# rev1.net
KiCad netlist of a schematic drawn in EAGLE
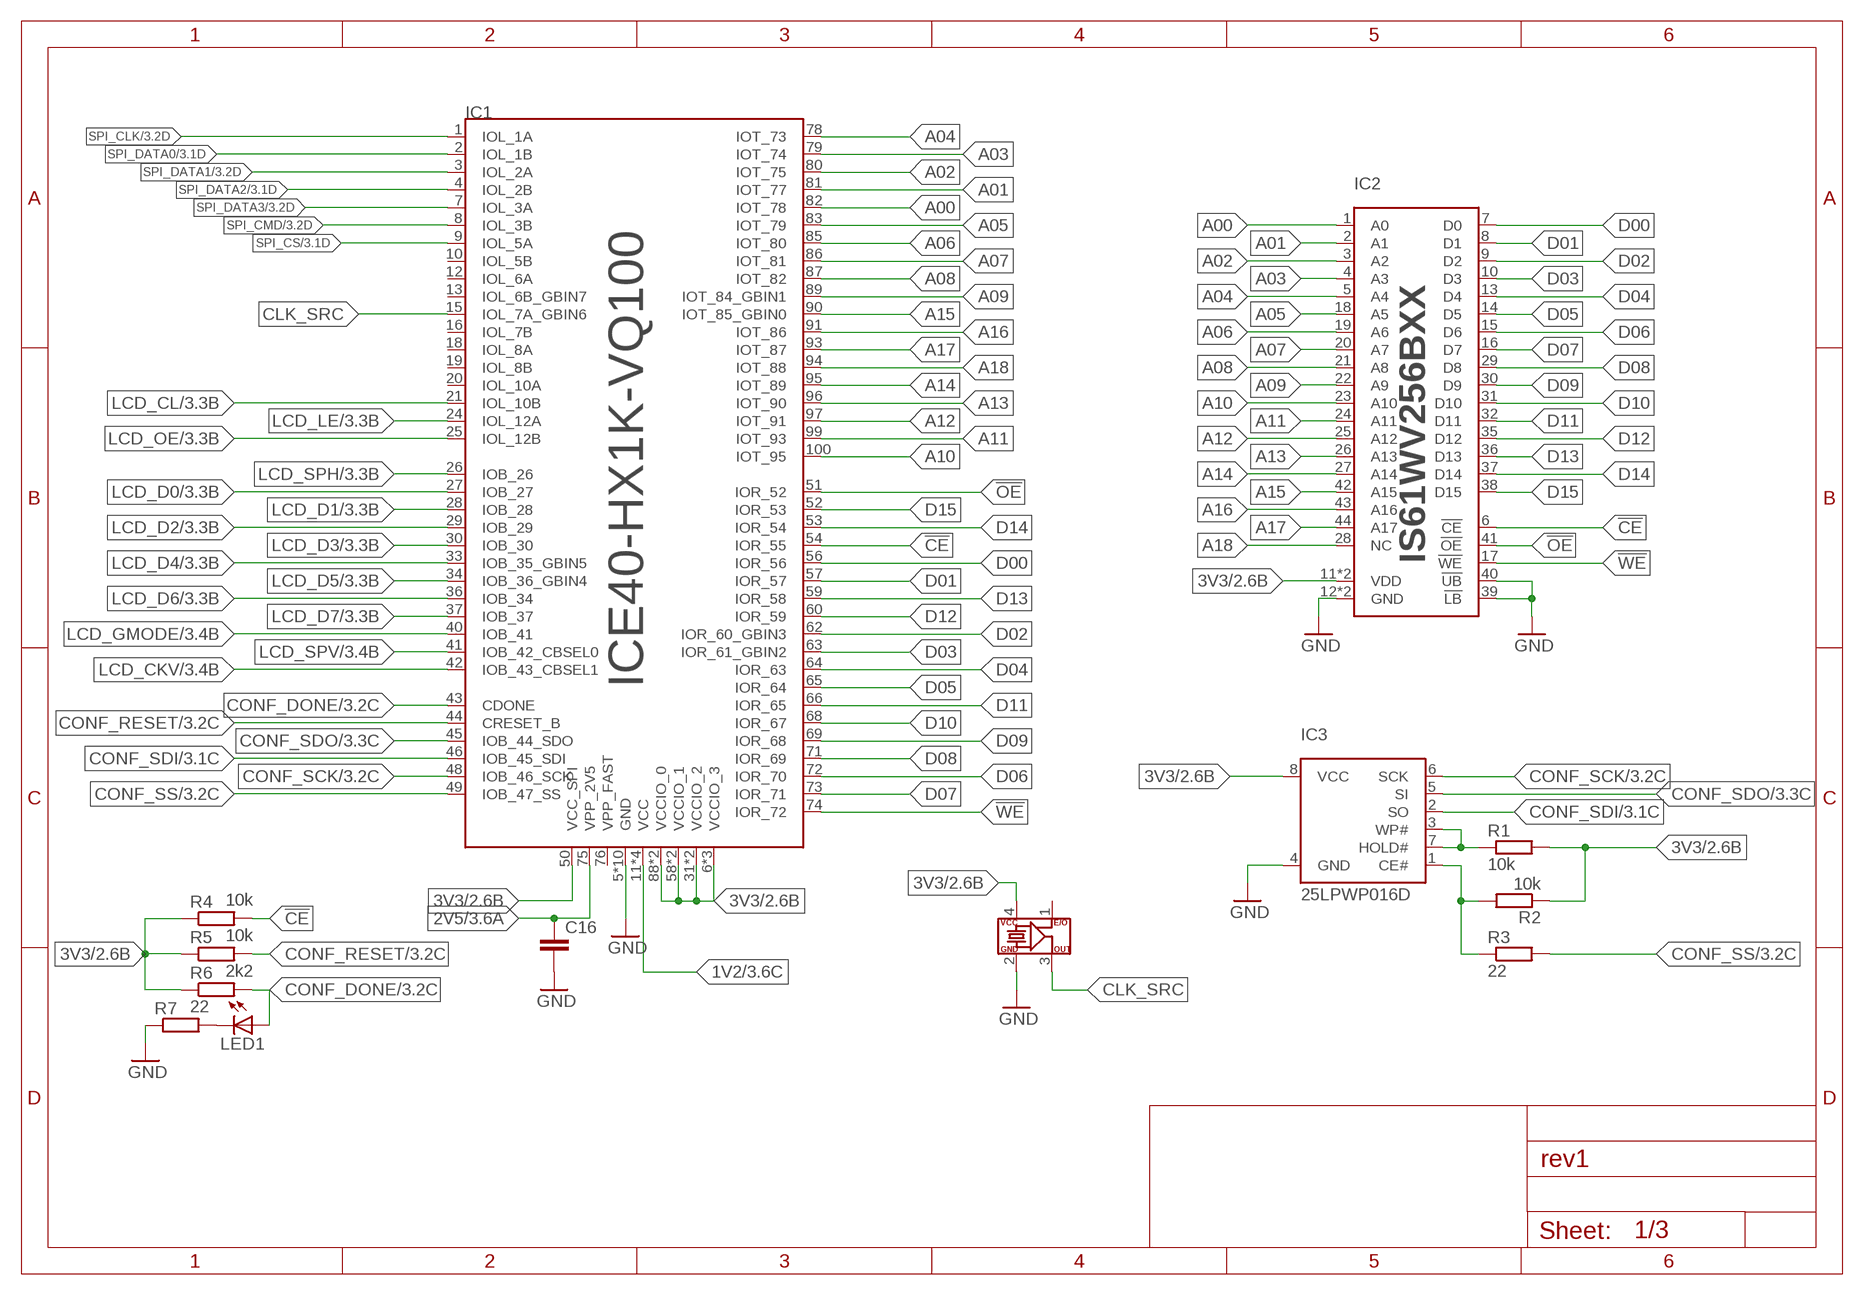
[diagram p0: schematic, sheet 1]
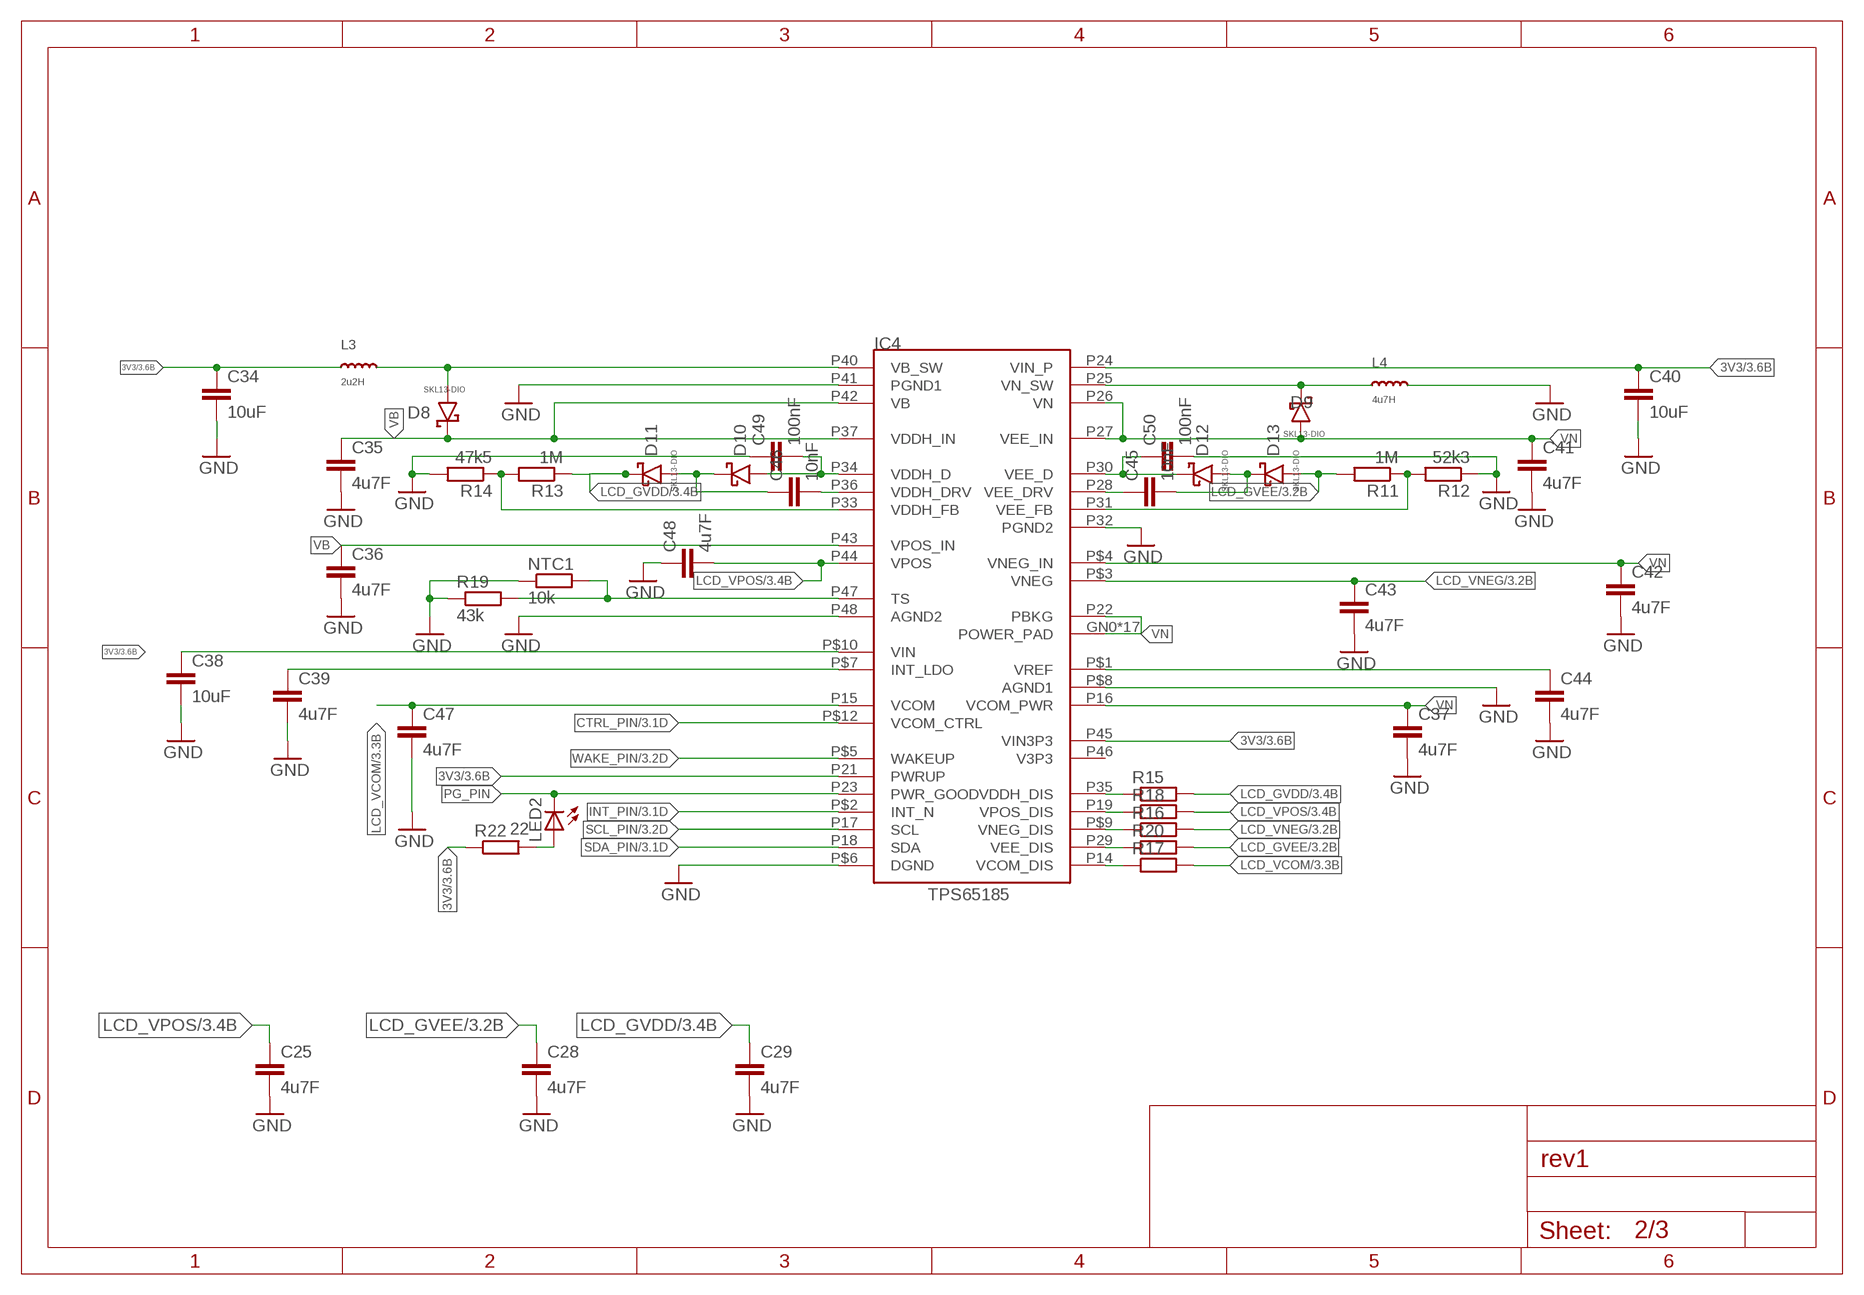
[diagram p1: schematic, sheet 2]
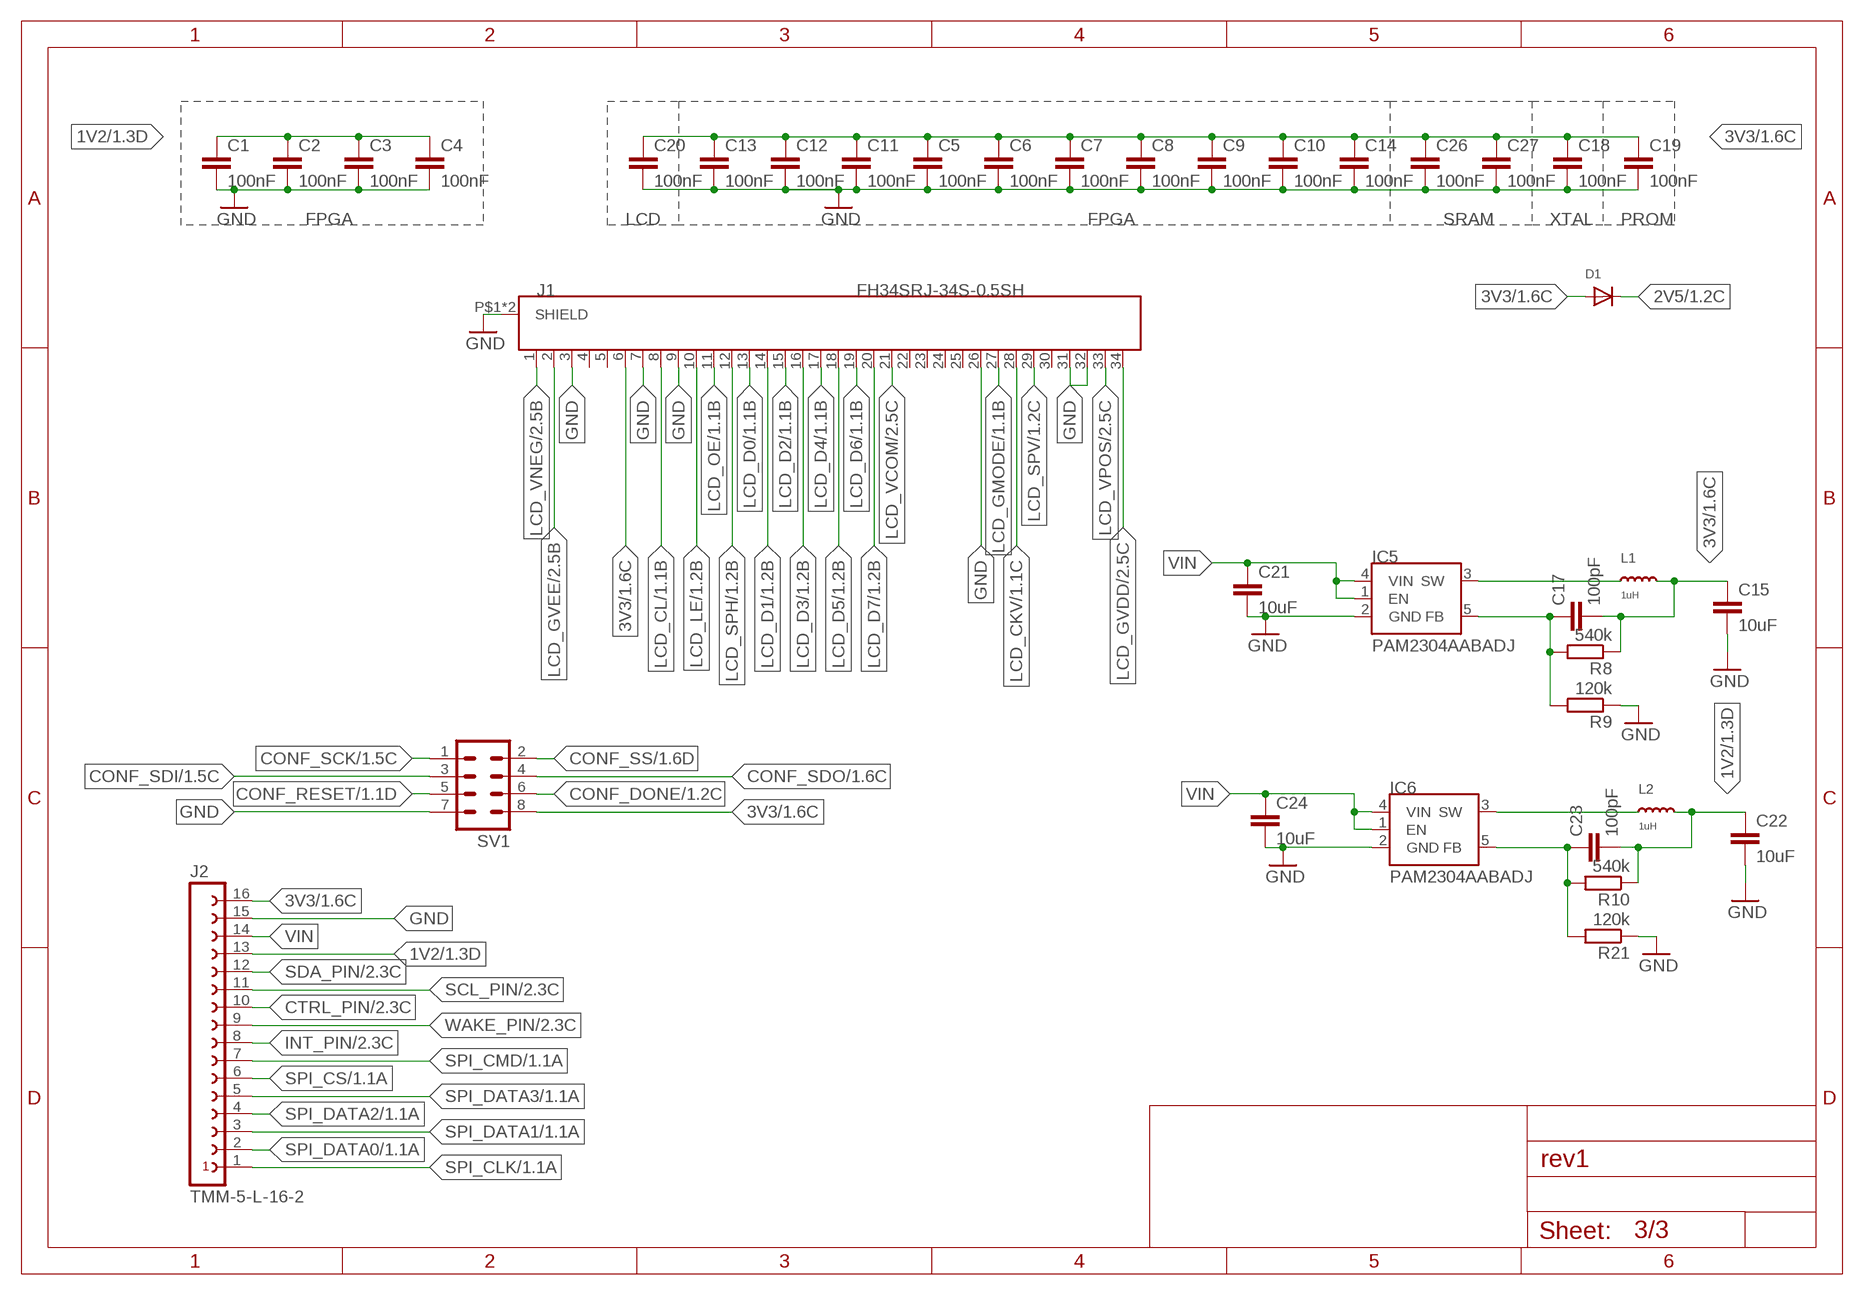
[diagram p2: schematic, sheet 3]

(export (version "E")
  (design (tool "Eeschema 10.0.6"))
  (components
    (comp (ref "C1")
      (value "100nF")
      (footprint "eagle-import:C0402")
      (libsource (lib "eagle-import") (part "C-EUC0402"))
    )
    (comp (ref "C2")
      (value "100nF")
      (footprint "eagle-import:C0402")
      (libsource (lib "eagle-import") (part "C-EUC0402"))
    )
    (comp (ref "C3")
      (value "100nF")
      (footprint "eagle-import:C0402")
      (libsource (lib "eagle-import") (part "C-EUC0402"))
    )
    (comp (ref "C4")
      (value "100nF")
      (footprint "eagle-import:C0402")
      (libsource (lib "eagle-import") (part "C-EUC0402"))
    )
    (comp (ref "C5")
      (value "100nF")
      (footprint "eagle-import:C0402")
      (libsource (lib "eagle-import") (part "C-EUC0402"))
    )
    (comp (ref "C6")
      (value "100nF")
      (footprint "eagle-import:C0402")
      (libsource (lib "eagle-import") (part "C-EUC0402"))
    )
    (comp (ref "C7")
      (value "100nF")
      (footprint "eagle-import:C0402")
      (libsource (lib "eagle-import") (part "C-EUC0402"))
    )
    (comp (ref "C8")
      (value "100nF")
      (footprint "eagle-import:C0402")
      (libsource (lib "eagle-import") (part "C-EUC0402"))
    )
    (comp (ref "C9")
      (value "100nF")
      (footprint "eagle-import:C0402")
      (libsource (lib "eagle-import") (part "C-EUC0402"))
    )
    (comp (ref "C10")
      (value "100nF")
      (footprint "eagle-import:C0402")
      (libsource (lib "eagle-import") (part "C-EUC0402"))
    )
    (comp (ref "C11")
      (value "100nF")
      (footprint "eagle-import:C0402")
      (libsource (lib "eagle-import") (part "C-EUC0402"))
    )
    (comp (ref "C12")
      (value "100nF")
      (footprint "eagle-import:C0402")
      (libsource (lib "eagle-import") (part "C-EUC0402"))
    )
    (comp (ref "C13")
      (value "100nF")
      (footprint "eagle-import:C0402")
      (libsource (lib "eagle-import") (part "C-EUC0402"))
    )
    (comp (ref "C14")
      (value "100nF")
      (footprint "eagle-import:C0402")
      (libsource (lib "eagle-import") (part "C-EUC0402"))
    )
    (comp (ref "C15")
      (value "10uF")
      (footprint "eagle-import:C0603")
      (libsource (lib "eagle-import") (part "C-EUC0603"))
    )
    (comp (ref "C17")
      (value "100pF")
      (footprint "eagle-import:C0402")
      (libsource (lib "eagle-import") (part "C-EUC0402"))
    )
    (comp (ref "C18")
      (value "100nF")
      (footprint "eagle-import:C0402")
      (libsource (lib "eagle-import") (part "C-EUC0402"))
    )
    (comp (ref "C19")
      (value "100nF")
      (footprint "eagle-import:C0402")
      (libsource (lib "eagle-import") (part "C-EUC0402"))
    )
    (comp (ref "C20")
      (value "100nF")
      (footprint "eagle-import:C0402")
      (libsource (lib "eagle-import") (part "C-EUC0402"))
    )
    (comp (ref "C21")
      (value "10uF")
      (footprint "eagle-import:C0603")
      (libsource (lib "eagle-import") (part "C-EUC0603"))
    )
    (comp (ref "C22")
      (value "10uF")
      (footprint "eagle-import:C0603")
      (libsource (lib "eagle-import") (part "C-EUC0603"))
    )
    (comp (ref "C23")
      (value "100pF")
      (footprint "eagle-import:C0402")
      (libsource (lib "eagle-import") (part "C-EUC0402"))
    )
    (comp (ref "C24")
      (value "10uF")
      (footprint "eagle-import:C0603")
      (libsource (lib "eagle-import") (part "C-EUC0603"))
    )
    (comp (ref "C26")
      (value "100nF")
      (footprint "eagle-import:C0402")
      (libsource (lib "eagle-import") (part "C-EUC0402"))
    )
    (comp (ref "C27")
      (value "100nF")
      (footprint "eagle-import:C0402")
      (libsource (lib "eagle-import") (part "C-EUC0402"))
    )
    (comp (ref "D1")
      (value "DIODESOD-123")
      (footprint "eagle-import:SOD-123")
      (libsource (lib "eagle-import") (part "DIODESOD-123"))
    )
    (comp (ref "IC5")
      (value "PAM2304AABADJ")
      (footprint "eagle-import:TSOT25")
      (libsource (lib "eagle-import") (part "PAM2304AABADJ"))
    )
    (comp (ref "IC6")
      (value "PAM2304AABADJ")
      (footprint "eagle-import:TSOT25")
      (libsource (lib "eagle-import") (part "PAM2304AABADJ"))
    )
    (comp (ref "J1")
      (value "FH34SRJ-34S-0.5SH")
      (footprint "eagle-import:FH34SRJ-34S-0.5SH")
      (libsource (lib "eagle-import") (part "FH34SRJ-34S-0.5SH"))
    )
    (comp (ref "J2")
      (value "TMM-5-L-16-2")
      (footprint "eagle-import:TMM-5-L-16-2")
      (libsource (lib "eagle-import") (part "TMM-5-L-16-2"))
    )
    (comp (ref "L1")
      (value "1uH")
      (footprint "eagle-import:3015")
      (libsource (lib "eagle-import") (part "DJNR-3015-1R0"))
    )
    (comp (ref "L2")
      (value "1uH")
      (footprint "eagle-import:3015")
      (libsource (lib "eagle-import") (part "DJNR-3015-1R0"))
    )
    (comp (ref "R8")
      (value "540k")
      (footprint "eagle-import:R0402")
      (libsource (lib "eagle-import") (part "R-EU_R0402"))
    )
    (comp (ref "R9")
      (value "120k")
      (footprint "eagle-import:R0402")
      (libsource (lib "eagle-import") (part "R-EU_R0402"))
    )
    (comp (ref "R10")
      (value "540k")
      (footprint "eagle-import:R0402")
      (libsource (lib "eagle-import") (part "R-EU_R0402"))
    )
    (comp (ref "R21")
      (value "120k")
      (footprint "eagle-import:R0402")
      (libsource (lib "eagle-import") (part "R-EU_R0402"))
    )
    (comp (ref "SV1")
      (value "MA04-2")
      (footprint "eagle-import:MA04-2")
      (libsource (lib "eagle-import") (part "MA04-2"))
    )
    (comp (ref "C16")
      (value "C-EUC0402")
      (footprint "eagle-import:C0402")
      (libsource (lib "eagle-import") (part "C-EUC0402"))
    )
    (comp (ref "IC1")
      (value "ICE40-HX1K-VQ100")
      (footprint "eagle-import:VQ100")
      (libsource (lib "eagle-import") (part "ICE40-HX1K-VQ100"))
    )
    (comp (ref "IC2")
      (value "IS61WV256BXX")
      (footprint "eagle-import:TSOP-2")
      (libsource (lib "eagle-import") (part "IS61WV256BXX"))
    )
    (comp (ref "IC3")
      (value "25LPWP016D")
      (footprint "eagle-import:SOP08")
      (libsource (lib "eagle-import") (part "25LPWP016D"))
    )
    (comp (ref "LED1")
      (value "LEDCHIP-LED0603")
      (footprint "eagle-import:CHIP-LED0603")
      (libsource (lib "eagle-import") (part "LEDCHIP-LED0603"))
    )
    (comp (ref "R1")
      (value "10k")
      (footprint "eagle-import:R0402")
      (libsource (lib "eagle-import") (part "R-EU_R0402"))
    )
    (comp (ref "R2")
      (value "10k")
      (footprint "eagle-import:R0603")
      (libsource (lib "eagle-import") (part "R-EU_R0603"))
    )
    (comp (ref "R3")
      (value "22")
      (footprint "eagle-import:R0402")
      (libsource (lib "eagle-import") (part "R-EU_R0402"))
    )
    (comp (ref "R4")
      (value "10k")
      (footprint "eagle-import:R0402")
      (libsource (lib "eagle-import") (part "R-EU_R0402"))
    )
    (comp (ref "R5")
      (value "10k")
      (footprint "eagle-import:R0402")
      (libsource (lib "eagle-import") (part "R-EU_R0402"))
    )
    (comp (ref "R6")
      (value "2k2")
      (footprint "eagle-import:R0402")
      (libsource (lib "eagle-import") (part "R-EU_R0402"))
    )
    (comp (ref "R7")
      (value "22")
      (footprint "eagle-import:R0402")
      (libsource (lib "eagle-import") (part "R-EU_R0402"))
    )
    (comp (ref "X1")
      (value "DSC61XX")
      (footprint "eagle-import:3225")
      (libsource (lib "eagle-import") (part "DSC61XX"))
    )
    (comp (ref "C25")
      (value "4u7F")
      (footprint "eagle-import:C0603")
      (libsource (lib "eagle-import") (part "C-EUC0603"))
    )
    (comp (ref "C28")
      (value "4u7F")
      (footprint "eagle-import:C0603")
      (libsource (lib "eagle-import") (part "C-EUC0603"))
    )
    (comp (ref "C29")
      (value "4u7F")
      (footprint "eagle-import:C0603")
      (libsource (lib "eagle-import") (part "C-EUC0603"))
    )
    (comp (ref "C34")
      (value "10uF")
      (footprint "eagle-import:C0805")
      (libsource (lib "eagle-import") (part "C-EUC0805"))
    )
    (comp (ref "C35")
      (value "4u7F")
      (footprint "eagle-import:C0805")
      (libsource (lib "eagle-import") (part "C-EUC0805"))
    )
    (comp (ref "C36")
      (value "4u7F")
      (footprint "eagle-import:C0805")
      (libsource (lib "eagle-import") (part "C-EUC0805"))
    )
    (comp (ref "C37")
      (value "4u7F")
      (footprint "eagle-import:C0805")
      (libsource (lib "eagle-import") (part "C-EUC0805"))
    )
    (comp (ref "C38")
      (value "10uF")
      (footprint "eagle-import:C0805")
      (libsource (lib "eagle-import") (part "C-EUC0805"))
    )
    (comp (ref "C39")
      (value "4u7F")
      (footprint "eagle-import:C0603")
      (libsource (lib "eagle-import") (part "C-EUC0603"))
    )
    (comp (ref "C40")
      (value "10uF")
      (footprint "eagle-import:C0805")
      (libsource (lib "eagle-import") (part "C-EUC0805"))
    )
    (comp (ref "C41")
      (value "4u7F")
      (footprint "eagle-import:C0805")
      (libsource (lib "eagle-import") (part "C-EUC0805"))
    )
    (comp (ref "C42")
      (value "4u7F")
      (footprint "eagle-import:C0805")
      (libsource (lib "eagle-import") (part "C-EUC0805"))
    )
    (comp (ref "C43")
      (value "4u7F")
      (footprint "eagle-import:C0805")
      (libsource (lib "eagle-import") (part "C-EUC0805"))
    )
    (comp (ref "C44")
      (value "4u7F")
      (footprint "eagle-import:C0603")
      (libsource (lib "eagle-import") (part "C-EUC0603"))
    )
    (comp (ref "C45")
      (value "10nF")
      (footprint "eagle-import:C0402")
      (libsource (lib "eagle-import") (part "C-EUC0402"))
    )
    (comp (ref "C46")
      (value "10nF")
      (footprint "eagle-import:C0402")
      (libsource (lib "eagle-import") (part "C-EUC0402"))
    )
    (comp (ref "C47")
      (value "4u7F")
      (footprint "eagle-import:C0603")
      (libsource (lib "eagle-import") (part "C-EUC0603"))
    )
    (comp (ref "C48")
      (value "4u7F")
      (footprint "eagle-import:C0805")
      (libsource (lib "eagle-import") (part "C-EUC0805"))
    )
    (comp (ref "C49")
      (value "100nF")
      (footprint "eagle-import:C0402")
      (libsource (lib "eagle-import") (part "C-EUC0402"))
    )
    (comp (ref "C50")
      (value "100nF")
      (footprint "eagle-import:C0402")
      (libsource (lib "eagle-import") (part "C-EUC0402"))
    )
    (comp (ref "D8")
      (value "SKL13-DIO")
      (footprint "eagle-import:SOD523")
      (libsource (lib "eagle-import") (part "RB520S30T"))
    )
    (comp (ref "D9")
      (value "SKL13-DIO")
      (footprint "eagle-import:SOD523")
      (libsource (lib "eagle-import") (part "RB520S30T"))
    )
    (comp (ref "D10")
      (value "SKL13-DIO")
      (footprint "eagle-import:SOD523")
      (libsource (lib "eagle-import") (part "RB520S30T"))
    )
    (comp (ref "D11")
      (value "SKL13-DIO")
      (footprint "eagle-import:SOD523")
      (libsource (lib "eagle-import") (part "RB520S30T"))
    )
    (comp (ref "D12")
      (value "SKL13-DIO")
      (footprint "eagle-import:SOD523")
      (libsource (lib "eagle-import") (part "RB520S30T"))
    )
    (comp (ref "D13")
      (value "SKL13-DIO")
      (footprint "eagle-import:SOD523")
      (libsource (lib "eagle-import") (part "RB520S30T"))
    )
    (comp (ref "IC4")
      (value "TPS65185")
      (footprint "eagle-import:RGZ")
      (libsource (lib "eagle-import") (part "TPS65185"))
    )
    (comp (ref "L3")
      (value "2u2H")
      (footprint "eagle-import:3015")
      (libsource (lib "eagle-import") (part "DJNR-3015-2R2"))
    )
    (comp (ref "L4")
      (value "4u7H")
      (footprint "eagle-import:3015")
      (libsource (lib "eagle-import") (part "DJNR-3015-1R0"))
    )
    (comp (ref "LED2")
      (value "LEDCHIP-LED0603")
      (footprint "eagle-import:CHIP-LED0603")
      (libsource (lib "eagle-import") (part "LEDCHIP-LED0603"))
    )
    (comp (ref "NTC1")
      (value "10k")
      (footprint "eagle-import:R0603")
      (libsource (lib "eagle-import") (part "R-EU_R0603"))
    )
    (comp (ref "R11")
      (value "1M")
      (footprint "eagle-import:R0603")
      (libsource (lib "eagle-import") (part "R-EU_R0603"))
    )
    (comp (ref "R12")
      (value "52k3")
      (footprint "eagle-import:R0603")
      (libsource (lib "eagle-import") (part "R-EU_R0603"))
    )
    (comp (ref "R13")
      (value "1M")
      (footprint "eagle-import:R0603")
      (libsource (lib "eagle-import") (part "R-EU_R0603"))
    )
    (comp (ref "R14")
      (value "47k5")
      (footprint "eagle-import:R0603")
      (libsource (lib "eagle-import") (part "R-EU_R0603"))
    )
    (comp (ref "R15")
      (value "R-EU_R0603")
      (footprint "eagle-import:R0603")
      (libsource (lib "eagle-import") (part "R-EU_R0603"))
    )
    (comp (ref "R16")
      (value "R-EU_R0603")
      (footprint "eagle-import:R0603")
      (libsource (lib "eagle-import") (part "R-EU_R0603"))
    )
    (comp (ref "R17")
      (value "R-EU_R0603")
      (footprint "eagle-import:R0603")
      (libsource (lib "eagle-import") (part "R-EU_R0603"))
    )
    (comp (ref "R18")
      (value "R-EU_R0603")
      (footprint "eagle-import:R0603")
      (libsource (lib "eagle-import") (part "R-EU_R0603"))
    )
    (comp (ref "R19")
      (value "43k")
      (footprint "eagle-import:R0603")
      (libsource (lib "eagle-import") (part "R-EU_R0603"))
    )
    (comp (ref "R20")
      (value "R-EU_R0603")
      (footprint "eagle-import:R0603")
      (libsource (lib "eagle-import") (part "R-EU_R0603"))
    )
    (comp (ref "R22")
      (value "22")
      (footprint "eagle-import:R0402")
      (libsource (lib "eagle-import") (part "R-EU_R0402"))
    )
  )
  (nets
    (net (code "1") (name "1V2") (class "Default")
      (node (ref "C1") (pin "1") (pinfunction "1_1") (pintype "passive"))
      (node (ref "C2") (pin "1") (pinfunction "1_1") (pintype "passive"))
      (node (ref "C22") (pin "1") (pinfunction "1_1") (pintype "passive"))
      (node (ref "C23") (pin "2") (pinfunction "2_2") (pintype "passive"))
      (node (ref "C3") (pin "1") (pinfunction "1_1") (pintype "passive"))
      (node (ref "C4") (pin "1") (pinfunction "1_1") (pintype "passive"))
      (node (ref "IC1") (pin "11") (pinfunction "VCC_11") (pintype "bidirectional"))
      (node (ref "IC1") (pin "35") (pinfunction "VCC_35") (pintype "bidirectional"))
      (node (ref "IC1") (pin "61") (pinfunction "VCC_61") (pintype "bidirectional"))
      (node (ref "IC1") (pin "77") (pinfunction "VCC_77") (pintype "bidirectional"))
      (node (ref "J2") (pin "13") (pinfunction "13_13") (pintype "passive"))
      (node (ref "L2") (pin "P$2") (pinfunction "P$2_P$2") (pintype "bidirectional"))
      (node (ref "R10") (pin "1") (pinfunction "1_1") (pintype "passive"))
    )
    (net (code "2") (name "2V5") (class "Default")
      (node (ref "C16") (pin "1") (pinfunction "1_1") (pintype "passive"))
      (node (ref "D1") (pin "C") (pinfunction "C_C") (pintype "passive"))
      (node (ref "IC1") (pin "75") (pinfunction "VPP_2V5_75") (pintype "bidirectional"))
    )
    (net (code "3") (name "3V3") (class "Default")
      (node (ref "C10") (pin "1") (pinfunction "1_1") (pintype "passive"))
      (node (ref "C11") (pin "1") (pinfunction "1_1") (pintype "passive"))
      (node (ref "C12") (pin "1") (pinfunction "1_1") (pintype "passive"))
      (node (ref "C13") (pin "1") (pinfunction "1_1") (pintype "passive"))
      (node (ref "C14") (pin "1") (pinfunction "1_1") (pintype "passive"))
      (node (ref "C15") (pin "1") (pinfunction "1_1") (pintype "passive"))
      (node (ref "C17") (pin "2") (pinfunction "2_2") (pintype "passive"))
      (node (ref "C18") (pin "1") (pinfunction "1_1") (pintype "passive"))
      (node (ref "C19") (pin "1") (pinfunction "1_1") (pintype "passive"))
      (node (ref "C20") (pin "1") (pinfunction "1_1") (pintype "passive"))
      (node (ref "C26") (pin "1") (pinfunction "1_1") (pintype "passive"))
      (node (ref "C27") (pin "1") (pinfunction "1_1") (pintype "passive"))
      (node (ref "C34") (pin "1") (pinfunction "1_1") (pintype "passive"))
      (node (ref "C38") (pin "1") (pinfunction "1_1") (pintype "passive"))
      (node (ref "C40") (pin "1") (pinfunction "1_1") (pintype "passive"))
      (node (ref "C5") (pin "1") (pinfunction "1_1") (pintype "passive"))
      (node (ref "C6") (pin "1") (pinfunction "1_1") (pintype "passive"))
      (node (ref "C7") (pin "1") (pinfunction "1_1") (pintype "passive"))
      (node (ref "C8") (pin "1") (pinfunction "1_1") (pintype "passive"))
      (node (ref "C9") (pin "1") (pinfunction "1_1") (pintype "passive"))
      (node (ref "D1") (pin "A") (pinfunction "A_A") (pintype "passive"))
      (node (ref "IC1") (pin "14") (pinfunction "VCCIO_3_14") (pintype "bidirectional"))
      (node (ref "IC1") (pin "22") (pinfunction "VCCIO_3_22") (pintype "bidirectional"))
      (node (ref "IC1") (pin "31") (pinfunction "VCCIO_2_31") (pintype "bidirectional"))
      (node (ref "IC1") (pin "38") (pinfunction "VCCIO_2_38") (pintype "bidirectional"))
      (node (ref "IC1") (pin "50") (pinfunction "VCC_SPI_50") (pintype "bidirectional"))
      (node (ref "IC1") (pin "58") (pinfunction "VCCIO_1_58") (pintype "bidirectional"))
      (node (ref "IC1") (pin "6") (pinfunction "VCCIO_3_6") (pintype "bidirectional"))
      (node (ref "IC1") (pin "67") (pinfunction "VCCIO_1_67") (pintype "bidirectional"))
      (node (ref "IC1") (pin "88") (pinfunction "VCCIO_0_88") (pintype "bidirectional"))
      (node (ref "IC1") (pin "92") (pinfunction "VCCIO_0_92") (pintype "bidirectional"))
      (node (ref "IC2") (pin "11") (pinfunction "VDD_11") (pintype "bidirectional"))
      (node (ref "IC2") (pin "33") (pinfunction "VDD_33") (pintype "bidirectional"))
      (node (ref "IC3") (pin "8") (pinfunction "VCC_8") (pintype "bidirectional"))
      (node (ref "IC4") (pin "P$10") (pinfunction "VIN_P$10") (pintype "bidirectional"))
      (node (ref "IC4") (pin "P21") (pinfunction "PWRUP_P21") (pintype "bidirectional"))
      (node (ref "IC4") (pin "P24") (pinfunction "VIN_P_P24") (pintype "bidirectional"))
      (node (ref "IC4") (pin "P45") (pinfunction "VIN3P3_P45") (pintype "bidirectional"))
      (node (ref "J1") (pin "6") (pinfunction "P$6_6") (pintype "bidirectional"))
      (node (ref "J2") (pin "16") (pinfunction "16_16") (pintype "passive"))
      (node (ref "L1") (pin "P$2") (pinfunction "P$2_P$2") (pintype "bidirectional"))
      (node (ref "L3") (pin "P$1") (pinfunction "P$1_P$1") (pintype "bidirectional"))
      (node (ref "R1") (pin "2") (pinfunction "2_2") (pintype "passive"))
      (node (ref "R2") (pin "1") (pinfunction "1_1") (pintype "passive"))
      (node (ref "R22") (pin "1") (pinfunction "1_1") (pintype "passive"))
      (node (ref "R4") (pin "1") (pinfunction "1_1") (pintype "passive"))
      (node (ref "R5") (pin "1") (pinfunction "1_1") (pintype "passive"))
      (node (ref "R6") (pin "1") (pinfunction "1_1") (pintype "passive"))
      (node (ref "R8") (pin "1") (pinfunction "1_1") (pintype "passive"))
      (node (ref "SV1") (pin "8") (pinfunction "8_8") (pintype "passive"))
      (node (ref "X1") (pin "4") (pinfunction "4_4") (pintype "bidirectional"))
    )
    (net (code "4") (name "A00") (class "Default")
      (node (ref "IC1") (pin "82") (pinfunction "IOT_78_82") (pintype "bidirectional"))
      (node (ref "IC2") (pin "1") (pinfunction "A0_1") (pintype "bidirectional"))
    )
    (net (code "5") (name "A01") (class "Default")
      (node (ref "IC1") (pin "81") (pinfunction "IOT_77_81") (pintype "bidirectional"))
      (node (ref "IC2") (pin "2") (pinfunction "A1_2") (pintype "bidirectional"))
    )
    (net (code "6") (name "A02") (class "Default")
      (node (ref "IC1") (pin "80") (pinfunction "IOT_75_80") (pintype "bidirectional"))
      (node (ref "IC2") (pin "3") (pinfunction "A2_3") (pintype "bidirectional"))
    )
    (net (code "7") (name "A03") (class "Default")
      (node (ref "IC1") (pin "79") (pinfunction "IOT_74_79") (pintype "bidirectional"))
      (node (ref "IC2") (pin "4") (pinfunction "A3_4") (pintype "bidirectional"))
    )
    (net (code "8") (name "A04") (class "Default")
      (node (ref "IC1") (pin "78") (pinfunction "IOT_73_78") (pintype "bidirectional"))
      (node (ref "IC2") (pin "5") (pinfunction "A4_5") (pintype "bidirectional"))
    )
    (net (code "9") (name "A05") (class "Default")
      (node (ref "IC1") (pin "83") (pinfunction "IOT_79_83") (pintype "bidirectional"))
      (node (ref "IC2") (pin "18") (pinfunction "A5_18") (pintype "bidirectional"))
    )
    (net (code "10") (name "A06") (class "Default")
      (node (ref "IC1") (pin "85") (pinfunction "IOT_80_85") (pintype "bidirectional"))
      (node (ref "IC2") (pin "19") (pinfunction "A6_19") (pintype "bidirectional"))
    )
    (net (code "11") (name "A07") (class "Default")
      (node (ref "IC1") (pin "86") (pinfunction "IOT_81_86") (pintype "bidirectional"))
      (node (ref "IC2") (pin "20") (pinfunction "A7_20") (pintype "bidirectional"))
    )
    (net (code "12") (name "A08") (class "Default")
      (node (ref "IC1") (pin "87") (pinfunction "IOT_82_87") (pintype "bidirectional"))
      (node (ref "IC2") (pin "21") (pinfunction "A8_21") (pintype "bidirectional"))
    )
    (net (code "13") (name "A09") (class "Default")
      (node (ref "IC1") (pin "89") (pinfunction "IOT_84_GBIN1_89") (pintype "bidirectional"))
      (node (ref "IC2") (pin "22") (pinfunction "A9_22") (pintype "bidirectional"))
    )
    (net (code "14") (name "A10") (class "Default")
      (node (ref "IC1") (pin "100") (pinfunction "IOT_95_100") (pintype "bidirectional"))
      (node (ref "IC2") (pin "23") (pinfunction "A10_23") (pintype "bidirectional"))
    )
    (net (code "15") (name "A11") (class "Default")
      (node (ref "IC1") (pin "99") (pinfunction "IOT_93_99") (pintype "bidirectional"))
      (node (ref "IC2") (pin "24") (pinfunction "A11_24") (pintype "bidirectional"))
    )
    (net (code "16") (name "A12") (class "Default")
      (node (ref "IC1") (pin "97") (pinfunction "IOT_91_97") (pintype "bidirectional"))
      (node (ref "IC2") (pin "25") (pinfunction "A12_25") (pintype "bidirectional"))
    )
    (net (code "17") (name "A13") (class "Default")
      (node (ref "IC1") (pin "96") (pinfunction "IOT_90_96") (pintype "bidirectional"))
      (node (ref "IC2") (pin "26") (pinfunction "A13_26") (pintype "bidirectional"))
    )
    (net (code "18") (name "A14") (class "Default")
      (node (ref "IC1") (pin "95") (pinfunction "IOT_89_95") (pintype "bidirectional"))
      (node (ref "IC2") (pin "27") (pinfunction "A14_27") (pintype "bidirectional"))
    )
    (net (code "19") (name "A15") (class "Default")
      (node (ref "IC1") (pin "90") (pinfunction "IOT_85_GBIN0_90") (pintype "bidirectional"))
      (node (ref "IC2") (pin "42") (pinfunction "A15_42") (pintype "bidirectional"))
    )
    (net (code "20") (name "A16") (class "Default")
      (node (ref "IC1") (pin "91") (pinfunction "IOT_86_91") (pintype "bidirectional"))
      (node (ref "IC2") (pin "43") (pinfunction "A16_43") (pintype "bidirectional"))
    )
    (net (code "21") (name "A17") (class "Default")
      (node (ref "IC1") (pin "93") (pinfunction "IOT_87_93") (pintype "bidirectional"))
      (node (ref "IC2") (pin "44") (pinfunction "A17_44") (pintype "bidirectional"))
    )
    (net (code "22") (name "A18") (class "Default")
      (node (ref "IC1") (pin "94") (pinfunction "IOT_88_94") (pintype "bidirectional"))
      (node (ref "IC2") (pin "28") (pinfunction "NC_28") (pintype "bidirectional"))
    )
    (net (code "23") (name "CLK_SRC") (class "Default")
      (node (ref "IC1") (pin "15") (pinfunction "IOL_7A_GBIN6_15") (pintype "bidirectional"))
      (node (ref "X1") (pin "3") (pinfunction "3_3") (pintype "bidirectional"))
    )
    (net (code "24") (name "CONF_DONE") (class "Default")
      (node (ref "IC1") (pin "43") (pinfunction "CDONE_43") (pintype "bidirectional"))
      (node (ref "LED1") (pin "A") (pinfunction "A_A") (pintype "passive"))
      (node (ref "R6") (pin "2") (pinfunction "2_2") (pintype "passive"))
      (node (ref "SV1") (pin "6") (pinfunction "6_6") (pintype "passive"))
    )
    (net (code "25") (name "CONF_RESET") (class "Default")
      (node (ref "IC1") (pin "44") (pinfunction "CRESET_B_44") (pintype "bidirectional"))
      (node (ref "R5") (pin "2") (pinfunction "2_2") (pintype "passive"))
      (node (ref "SV1") (pin "5") (pinfunction "5_5") (pintype "passive"))
    )
    (net (code "26") (name "CONF_SCK") (class "Default")
      (node (ref "IC1") (pin "48") (pinfunction "IOB_46_SCK_48") (pintype "bidirectional"))
      (node (ref "IC3") (pin "6") (pinfunction "SCK_6") (pintype "bidirectional"))
      (node (ref "SV1") (pin "1") (pinfunction "1_1") (pintype "passive"))
    )
    (net (code "27") (name "CONF_SDI") (class "Default")
      (node (ref "IC1") (pin "46") (pinfunction "IOB_45_SDI_46") (pintype "bidirectional"))
      (node (ref "IC3") (pin "2") (pinfunction "SO_2") (pintype "bidirectional"))
      (node (ref "SV1") (pin "3") (pinfunction "3_3") (pintype "passive"))
    )
    (net (code "28") (name "CONF_SDO") (class "Default")
      (node (ref "IC1") (pin "45") (pinfunction "IOB_44_SDO_45") (pintype "bidirectional"))
      (node (ref "IC3") (pin "5") (pinfunction "SI_5") (pintype "bidirectional"))
      (node (ref "SV1") (pin "4") (pinfunction "4_4") (pintype "passive"))
    )
    (net (code "29") (name "CONF_SS") (class "Default")
      (node (ref "IC1") (pin "49") (pinfunction "IOB_47_SS_49") (pintype "bidirectional"))
      (node (ref "R3") (pin "2") (pinfunction "2_2") (pintype "passive"))
      (node (ref "SV1") (pin "2") (pinfunction "2_2") (pintype "passive"))
    )
    (net (code "30") (name "CTRL_PIN") (class "Default")
      (node (ref "IC4") (pin "P$12") (pinfunction "VCOM_CTRL_P$12") (pintype "bidirectional"))
      (node (ref "J2") (pin "10") (pinfunction "10_10") (pintype "passive"))
    )
    (net (code "31") (name "D00") (class "Default")
      (node (ref "IC1") (pin "56") (pinfunction "IOR_56_56") (pintype "bidirectional"))
      (node (ref "IC2") (pin "7") (pinfunction "D0_7") (pintype "bidirectional"))
    )
    (net (code "32") (name "D01") (class "Default")
      (node (ref "IC1") (pin "57") (pinfunction "IOR_57_57") (pintype "bidirectional"))
      (node (ref "IC2") (pin "8") (pinfunction "D1_8") (pintype "bidirectional"))
    )
    (net (code "33") (name "D02") (class "Default")
      (node (ref "IC1") (pin "62") (pinfunction "IOR_60_GBIN3_62") (pintype "bidirectional"))
      (node (ref "IC2") (pin "9") (pinfunction "D2_9") (pintype "bidirectional"))
    )
    (net (code "34") (name "D03") (class "Default")
      (node (ref "IC1") (pin "63") (pinfunction "IOR_61_GBIN2_63") (pintype "bidirectional"))
      (node (ref "IC2") (pin "10") (pinfunction "D3_10") (pintype "bidirectional"))
    )
    (net (code "35") (name "D04") (class "Default")
      (node (ref "IC1") (pin "64") (pinfunction "IOR_63_64") (pintype "bidirectional"))
      (node (ref "IC2") (pin "13") (pinfunction "D4_13") (pintype "bidirectional"))
    )
    (net (code "36") (name "D05") (class "Default")
      (node (ref "IC1") (pin "65") (pinfunction "IOR_64_65") (pintype "bidirectional"))
      (node (ref "IC2") (pin "14") (pinfunction "D5_14") (pintype "bidirectional"))
    )
    (net (code "37") (name "D06") (class "Default")
      (node (ref "IC1") (pin "72") (pinfunction "IOR_70_72") (pintype "bidirectional"))
      (node (ref "IC2") (pin "15") (pinfunction "D6_15") (pintype "bidirectional"))
    )
    (net (code "38") (name "D07") (class "Default")
      (node (ref "IC1") (pin "73") (pinfunction "IOR_71_73") (pintype "bidirectional"))
      (node (ref "IC2") (pin "16") (pinfunction "D7_16") (pintype "bidirectional"))
    )
    (net (code "39") (name "D08") (class "Default")
      (node (ref "IC1") (pin "71") (pinfunction "IOR_69_71") (pintype "bidirectional"))
      (node (ref "IC2") (pin "29") (pinfunction "D8_29") (pintype "bidirectional"))
    )
    (net (code "40") (name "D09") (class "Default")
      (node (ref "IC1") (pin "69") (pinfunction "IOR_68_69") (pintype "bidirectional"))
      (node (ref "IC2") (pin "30") (pinfunction "D9_30") (pintype "bidirectional"))
    )
    (net (code "41") (name "D10") (class "Default")
      (node (ref "IC1") (pin "68") (pinfunction "IOR_67_68") (pintype "bidirectional"))
      (node (ref "IC2") (pin "31") (pinfunction "D10_31") (pintype "bidirectional"))
    )
    (net (code "42") (name "D11") (class "Default")
      (node (ref "IC1") (pin "66") (pinfunction "IOR_65_66") (pintype "bidirectional"))
      (node (ref "IC2") (pin "32") (pinfunction "D11_32") (pintype "bidirectional"))
    )
    (net (code "43") (name "D12") (class "Default")
      (node (ref "IC1") (pin "60") (pinfunction "IOR_59_60") (pintype "bidirectional"))
      (node (ref "IC2") (pin "35") (pinfunction "D12_35") (pintype "bidirectional"))
    )
    (net (code "44") (name "D13") (class "Default")
      (node (ref "IC1") (pin "59") (pinfunction "IOR_58_59") (pintype "bidirectional"))
      (node (ref "IC2") (pin "36") (pinfunction "D13_36") (pintype "bidirectional"))
    )
    (net (code "45") (name "D14") (class "Default")
      (node (ref "IC1") (pin "53") (pinfunction "IOR_54_53") (pintype "bidirectional"))
      (node (ref "IC2") (pin "37") (pinfunction "D14_37") (pintype "bidirectional"))
    )
    (net (code "46") (name "D15") (class "Default")
      (node (ref "IC1") (pin "52") (pinfunction "IOR_53_52") (pintype "bidirectional"))
      (node (ref "IC2") (pin "38") (pinfunction "D15_38") (pintype "bidirectional"))
    )
    (net (code "47") (name "GND") (class "Default")
      (node (ref "C1") (pin "2") (pinfunction "2_2") (pintype "passive"))
      (node (ref "C10") (pin "2") (pinfunction "2_2") (pintype "passive"))
      (node (ref "C11") (pin "2") (pinfunction "2_2") (pintype "passive"))
      (node (ref "C12") (pin "2") (pinfunction "2_2") (pintype "passive"))
      (node (ref "C13") (pin "2") (pinfunction "2_2") (pintype "passive"))
      (node (ref "C14") (pin "2") (pinfunction "2_2") (pintype "passive"))
      (node (ref "C15") (pin "2") (pinfunction "2_2") (pintype "passive"))
      (node (ref "C16") (pin "2") (pinfunction "2_2") (pintype "passive"))
      (node (ref "C18") (pin "2") (pinfunction "2_2") (pintype "passive"))
      (node (ref "C19") (pin "2") (pinfunction "2_2") (pintype "passive"))
      (node (ref "C2") (pin "2") (pinfunction "2_2") (pintype "passive"))
      (node (ref "C20") (pin "2") (pinfunction "2_2") (pintype "passive"))
      (node (ref "C21") (pin "2") (pinfunction "2_2") (pintype "passive"))
      (node (ref "C22") (pin "2") (pinfunction "2_2") (pintype "passive"))
      (node (ref "C24") (pin "2") (pinfunction "2_2") (pintype "passive"))
      (node (ref "C25") (pin "2") (pinfunction "2_2") (pintype "passive"))
      (node (ref "C26") (pin "2") (pinfunction "2_2") (pintype "passive"))
      (node (ref "C27") (pin "2") (pinfunction "2_2") (pintype "passive"))
      (node (ref "C28") (pin "2") (pinfunction "2_2") (pintype "passive"))
      (node (ref "C29") (pin "2") (pinfunction "2_2") (pintype "passive"))
      (node (ref "C3") (pin "2") (pinfunction "2_2") (pintype "passive"))
      (node (ref "C34") (pin "2") (pinfunction "2_2") (pintype "passive"))
      (node (ref "C35") (pin "2") (pinfunction "2_2") (pintype "passive"))
      (node (ref "C36") (pin "2") (pinfunction "2_2") (pintype "passive"))
      (node (ref "C37") (pin "2") (pinfunction "2_2") (pintype "passive"))
      (node (ref "C38") (pin "2") (pinfunction "2_2") (pintype "passive"))
      (node (ref "C39") (pin "2") (pinfunction "2_2") (pintype "passive"))
      (node (ref "C4") (pin "2") (pinfunction "2_2") (pintype "passive"))
      (node (ref "C40") (pin "2") (pinfunction "2_2") (pintype "passive"))
      (node (ref "C41") (pin "2") (pinfunction "2_2") (pintype "passive"))
      (node (ref "C42") (pin "2") (pinfunction "2_2") (pintype "passive"))
      (node (ref "C43") (pin "2") (pinfunction "2_2") (pintype "passive"))
      (node (ref "C44") (pin "2") (pinfunction "2_2") (pintype "passive"))
      (node (ref "C47") (pin "2") (pinfunction "2_2") (pintype "passive"))
      (node (ref "C48") (pin "1") (pinfunction "1_1") (pintype "passive"))
      (node (ref "C49") (pin "1") (pinfunction "1_1") (pintype "passive"))
      (node (ref "C5") (pin "2") (pinfunction "2_2") (pintype "passive"))
      (node (ref "C50") (pin "2") (pinfunction "2_2") (pintype "passive"))
      (node (ref "C6") (pin "2") (pinfunction "2_2") (pintype "passive"))
      (node (ref "C7") (pin "2") (pinfunction "2_2") (pintype "passive"))
      (node (ref "C8") (pin "2") (pinfunction "2_2") (pintype "passive"))
      (node (ref "C9") (pin "2") (pinfunction "2_2") (pintype "passive"))
      (node (ref "IC1") (pin "17") (pinfunction "GND_17") (pintype "bidirectional"))
      (node (ref "IC1") (pin "23") (pinfunction "GND_23") (pintype "bidirectional"))
      (node (ref "IC1") (pin "32") (pinfunction "GND_32") (pintype "bidirectional"))
      (node (ref "IC1") (pin "39") (pinfunction "GND_39") (pintype "bidirectional"))
      (node (ref "IC1") (pin "47") (pinfunction "GND_47") (pintype "bidirectional"))
      (node (ref "IC1") (pin "5") (pinfunction "GND_5") (pintype "bidirectional"))
      (node (ref "IC1") (pin "55") (pinfunction "GND_55") (pintype "bidirectional"))
      (node (ref "IC1") (pin "70") (pinfunction "GND_70") (pintype "bidirectional"))
      (node (ref "IC1") (pin "84") (pinfunction "GND_84") (pintype "bidirectional"))
      (node (ref "IC1") (pin "98") (pinfunction "GND_98") (pintype "bidirectional"))
      (node (ref "IC2") (pin "12") (pinfunction "GND_12") (pintype "bidirectional"))
      (node (ref "IC2") (pin "34") (pinfunction "GND_34") (pintype "bidirectional"))
      (node (ref "IC2") (pin "39") (pinfunction "~{LB}_39") (pintype "bidirectional"))
      (node (ref "IC2") (pin "40") (pinfunction "~{UB}_40") (pintype "bidirectional"))
      (node (ref "IC3") (pin "4") (pinfunction "GND_4") (pintype "bidirectional"))
      (node (ref "IC4") (pin "P$6") (pinfunction "DGND_P$6") (pintype "bidirectional"))
      (node (ref "IC4") (pin "P$8") (pinfunction "AGND1_P$8") (pintype "bidirectional"))
      (node (ref "IC4") (pin "P32") (pinfunction "PGND2_P32") (pintype "bidirectional"))
      (node (ref "IC4") (pin "P41") (pinfunction "PGND1_P41") (pintype "bidirectional"))
      (node (ref "IC4") (pin "P48") (pinfunction "AGND2_P48") (pintype "bidirectional"))
      (node (ref "IC5") (pin "2") (pinfunction "GND_2") (pintype "bidirectional"))
      (node (ref "IC6") (pin "2") (pinfunction "GND_2") (pintype "bidirectional"))
      (node (ref "J1") (pin "26") (pinfunction "P$26_26") (pintype "bidirectional"))
      (node (ref "J1") (pin "3") (pinfunction "P$3_3") (pintype "bidirectional"))
      (node (ref "J1") (pin "31") (pinfunction "P$31_31") (pintype "bidirectional"))
      (node (ref "J1") (pin "32") (pinfunction "P$32_32") (pintype "bidirectional"))
      (node (ref "J1") (pin "7") (pinfunction "P$7_7") (pintype "bidirectional"))
      (node (ref "J1") (pin "9") (pinfunction "P$9_9") (pintype "bidirectional"))
      (node (ref "J1") (pin "P$1") (pinfunction "SHIELD_P$1") (pintype "bidirectional"))
      (node (ref "J1") (pin "P$2") (pinfunction "SHIELD_P$2") (pintype "bidirectional"))
      (node (ref "J2") (pin "15") (pinfunction "15_15") (pintype "passive"))
      (node (ref "L4") (pin "P$2") (pinfunction "P$2_P$2") (pintype "bidirectional"))
      (node (ref "NTC1") (pin "1") (pinfunction "1_1") (pintype "passive"))
      (node (ref "R12") (pin "1") (pinfunction "1_1") (pintype "passive"))
      (node (ref "R14") (pin "2") (pinfunction "2_2") (pintype "passive"))
      (node (ref "R19") (pin "1") (pinfunction "1_1") (pintype "passive"))
      (node (ref "R21") (pin "1") (pinfunction "1_1") (pintype "passive"))
      (node (ref "R7") (pin "1") (pinfunction "1_1") (pintype "passive"))
      (node (ref "R9") (pin "1") (pinfunction "1_1") (pintype "passive"))
      (node (ref "SV1") (pin "7") (pinfunction "7_7") (pintype "passive"))
      (node (ref "X1") (pin "2") (pinfunction "2_2") (pintype "bidirectional"))
    )
    (net (code "48") (name "INT_PIN") (class "Default")
      (node (ref "IC4") (pin "P$2") (pinfunction "INT_N_P$2") (pintype "bidirectional"))
      (node (ref "J2") (pin "8") (pinfunction "8_8") (pintype "passive"))
    )
    (net (code "49") (name "LCD_CKV") (class "Default")
      (node (ref "IC1") (pin "42") (pinfunction "IOB_43_CBSEL1_42") (pintype "bidirectional"))
      (node (ref "J1") (pin "28") (pinfunction "P$28_28") (pintype "bidirectional"))
    )
    (net (code "50") (name "LCD_CL") (class "Default")
      (node (ref "IC1") (pin "21") (pinfunction "IOL_10B_21") (pintype "bidirectional"))
      (node (ref "J1") (pin "8") (pinfunction "P$8_8") (pintype "bidirectional"))
    )
    (net (code "51") (name "LCD_D0") (class "Default")
      (node (ref "IC1") (pin "27") (pinfunction "IOB_27_27") (pintype "bidirectional"))
      (node (ref "J1") (pin "13") (pinfunction "P$13_13") (pintype "bidirectional"))
    )
    (net (code "52") (name "LCD_D1") (class "Default")
      (node (ref "IC1") (pin "28") (pinfunction "IOB_28_28") (pintype "bidirectional"))
      (node (ref "J1") (pin "14") (pinfunction "P$14_14") (pintype "bidirectional"))
    )
    (net (code "53") (name "LCD_D2") (class "Default")
      (node (ref "IC1") (pin "29") (pinfunction "IOB_29_29") (pintype "bidirectional"))
      (node (ref "J1") (pin "15") (pinfunction "P$15_15") (pintype "bidirectional"))
    )
    (net (code "54") (name "LCD_D3") (class "Default")
      (node (ref "IC1") (pin "30") (pinfunction "IOB_30_30") (pintype "bidirectional"))
      (node (ref "J1") (pin "16") (pinfunction "P$16_16") (pintype "bidirectional"))
    )
    (net (code "55") (name "LCD_D4") (class "Default")
      (node (ref "IC1") (pin "33") (pinfunction "IOB_35_GBIN5_33") (pintype "bidirectional"))
      (node (ref "J1") (pin "17") (pinfunction "P$17_17") (pintype "bidirectional"))
    )
    (net (code "56") (name "LCD_D5") (class "Default")
      (node (ref "IC1") (pin "34") (pinfunction "IOB_36_GBIN4_34") (pintype "bidirectional"))
      (node (ref "J1") (pin "18") (pinfunction "P$18_18") (pintype "bidirectional"))
    )
    (net (code "57") (name "LCD_D6") (class "Default")
      (node (ref "IC1") (pin "36") (pinfunction "IOB_34_36") (pintype "bidirectional"))
      (node (ref "J1") (pin "19") (pinfunction "P$19_19") (pintype "bidirectional"))
    )
    (net (code "58") (name "LCD_D7") (class "Default")
      (node (ref "IC1") (pin "37") (pinfunction "IOB_37_37") (pintype "bidirectional"))
      (node (ref "J1") (pin "20") (pinfunction "P$20_20") (pintype "bidirectional"))
    )
    (net (code "59") (name "LCD_GMODE") (class "Default")
      (node (ref "IC1") (pin "40") (pinfunction "IOB_41_40") (pintype "bidirectional"))
      (node (ref "J1") (pin "27") (pinfunction "P$27_27") (pintype "bidirectional"))
    )
    (net (code "60") (name "LCD_GVDD") (class "Default")
      (node (ref "C29") (pin "1") (pinfunction "1_1") (pintype "passive"))
      (node (ref "D11") (pin "C") (pinfunction "C_C") (pintype "bidirectional"))
      (node (ref "J1") (pin "34") (pinfunction "P$34_34") (pintype "bidirectional"))
      (node (ref "R13") (pin "1") (pinfunction "1_1") (pintype "passive"))
      (node (ref "R15") (pin "2") (pinfunction "2_2") (pintype "passive"))
    )
    (net (code "61") (name "LCD_GVEE") (class "Default")
      (node (ref "C28") (pin "1") (pinfunction "1_1") (pintype "passive"))
      (node (ref "D13") (pin "A") (pinfunction "A_A") (pintype "bidirectional"))
      (node (ref "J1") (pin "2") (pinfunction "P$2_2") (pintype "bidirectional"))
      (node (ref "R11") (pin "2") (pinfunction "2_2") (pintype "passive"))
      (node (ref "R20") (pin "2") (pinfunction "2_2") (pintype "passive"))
    )
    (net (code "62") (name "LCD_LE") (class "Default")
      (node (ref "IC1") (pin "24") (pinfunction "IOL_12A_24") (pintype "bidirectional"))
      (node (ref "J1") (pin "10") (pinfunction "P$10_10") (pintype "bidirectional"))
    )
    (net (code "63") (name "LCD_OE") (class "Default")
      (node (ref "IC1") (pin "25") (pinfunction "IOL_12B_25") (pintype "bidirectional"))
      (node (ref "J1") (pin "11") (pinfunction "P$11_11") (pintype "bidirectional"))
    )
    (net (code "64") (name "LCD_SPH") (class "Default")
      (node (ref "IC1") (pin "26") (pinfunction "IOB_26_26") (pintype "bidirectional"))
      (node (ref "J1") (pin "12") (pinfunction "P$12_12") (pintype "bidirectional"))
    )
    (net (code "65") (name "LCD_SPV") (class "Default")
      (node (ref "IC1") (pin "41") (pinfunction "IOB_42_CBSEL0_41") (pintype "bidirectional"))
      (node (ref "J1") (pin "29") (pinfunction "P$29_29") (pintype "bidirectional"))
    )
    (net (code "66") (name "LCD_VCOM") (class "Default")
      (node (ref "C47") (pin "1") (pinfunction "1_1") (pintype "passive"))
      (node (ref "IC4") (pin "P15") (pinfunction "VCOM_P15") (pintype "bidirectional"))
      (node (ref "J1") (pin "21") (pinfunction "P$21_21") (pintype "bidirectional"))
      (node (ref "R17") (pin "2") (pinfunction "2_2") (pintype "passive"))
    )
    (net (code "67") (name "LCD_VNEG") (class "Default")
      (node (ref "C43") (pin "1") (pinfunction "1_1") (pintype "passive"))
      (node (ref "IC4") (pin "P$3") (pinfunction "VNEG_P$3") (pintype "bidirectional"))
      (node (ref "J1") (pin "1") (pinfunction "P$1_1") (pintype "bidirectional"))
      (node (ref "R16") (pin "2") (pinfunction "2_2") (pintype "passive"))
    )
    (net (code "68") (name "LCD_VPOS") (class "Default")
      (node (ref "C25") (pin "1") (pinfunction "1_1") (pintype "passive"))
      (node (ref "C48") (pin "2") (pinfunction "2_2") (pintype "passive"))
      (node (ref "IC4") (pin "P44") (pinfunction "VPOS_P44") (pintype "bidirectional"))
      (node (ref "J1") (pin "33") (pinfunction "P$33_33") (pintype "bidirectional"))
      (node (ref "R18") (pin "2") (pinfunction "2_2") (pintype "passive"))
    )
    (net (code "69") (name "Net-(C45-Pad2)") (class "Default")
      (node (ref "C45") (pin "2") (pinfunction "2_2") (pintype "passive"))
      (node (ref "D12") (pin "A") (pinfunction "A_A") (pintype "bidirectional"))
      (node (ref "D13") (pin "C") (pinfunction "C_C") (pintype "bidirectional"))
    )
    (net (code "70") (name "Net-(C46-Pad1)") (class "Default")
      (node (ref "C46") (pin "1") (pinfunction "1_1") (pintype "passive"))
      (node (ref "D10") (pin "C") (pinfunction "C_C") (pintype "bidirectional"))
      (node (ref "D11") (pin "A") (pinfunction "A_A") (pintype "bidirectional"))
    )
    (net (code "71") (name "Net-(IC3-CE#)") (class "Default")
      (node (ref "IC3") (pin "1") (pinfunction "CE#_1") (pintype "bidirectional"))
      (node (ref "R2") (pin "2") (pinfunction "2_2") (pintype "passive"))
      (node (ref "R3") (pin "1") (pinfunction "1_1") (pintype "passive"))
    )
    (net (code "72") (name "Net-(IC3-HOLD#)") (class "Default")
      (node (ref "IC3") (pin "3") (pinfunction "WP#_3") (pintype "bidirectional"))
      (node (ref "IC3") (pin "7") (pinfunction "HOLD#_7") (pintype "bidirectional"))
      (node (ref "R1") (pin "1") (pinfunction "1_1") (pintype "passive"))
    )
    (net (code "73") (name "Net-(IC4-INT_LDO)") (class "Default")
      (node (ref "C39") (pin "1") (pinfunction "1_1") (pintype "passive"))
      (node (ref "IC4") (pin "P$7") (pinfunction "INT_LDO_P$7") (pintype "bidirectional"))
    )
    (net (code "74") (name "Net-(IC4-TS)") (class "Default")
      (node (ref "IC4") (pin "P47") (pinfunction "TS_P47") (pintype "bidirectional"))
      (node (ref "NTC1") (pin "2") (pinfunction "2_2") (pintype "passive"))
      (node (ref "R19") (pin "2") (pinfunction "2_2") (pintype "passive"))
    )
    (net (code "75") (name "Net-(IC4-VB_SW)") (class "Default")
      (node (ref "D8") (pin "A") (pinfunction "A_A") (pintype "bidirectional"))
      (node (ref "IC4") (pin "P40") (pinfunction "VB_SW_P40") (pintype "bidirectional"))
      (node (ref "L3") (pin "P$2") (pinfunction "P$2_P$2") (pintype "bidirectional"))
    )
    (net (code "76") (name "Net-(IC4-VCOM_DIS)") (class "Default")
      (node (ref "IC4") (pin "P14") (pinfunction "VCOM_DIS_P14") (pintype "bidirectional"))
      (node (ref "R17") (pin "1") (pinfunction "1_1") (pintype "passive"))
    )
    (net (code "77") (name "Net-(IC4-VDDH_D)") (class "Default")
      (node (ref "C49") (pin "2") (pinfunction "2_2") (pintype "passive"))
      (node (ref "D10") (pin "A") (pinfunction "A_A") (pintype "bidirectional"))
      (node (ref "IC4") (pin "P34") (pinfunction "VDDH_D_P34") (pintype "bidirectional"))
    )
    (net (code "78") (name "Net-(IC4-VDDH_DIS)") (class "Default")
      (node (ref "IC4") (pin "P35") (pinfunction "VDDH_DIS_P35") (pintype "bidirectional"))
      (node (ref "R15") (pin "1") (pinfunction "1_1") (pintype "passive"))
    )
    (net (code "79") (name "Net-(IC4-VDDH_DRV)") (class "Default")
      (node (ref "C46") (pin "2") (pinfunction "2_2") (pintype "passive"))
      (node (ref "IC4") (pin "P36") (pinfunction "VDDH_DRV_P36") (pintype "bidirectional"))
    )
    (net (code "80") (name "Net-(IC4-VDDH_FB)") (class "Default")
      (node (ref "IC4") (pin "P33") (pinfunction "VDDH_FB_P33") (pintype "bidirectional"))
      (node (ref "R13") (pin "2") (pinfunction "2_2") (pintype "passive"))
      (node (ref "R14") (pin "1") (pinfunction "1_1") (pintype "passive"))
    )
    (net (code "81") (name "Net-(IC4-VEE_D)") (class "Default")
      (node (ref "C50") (pin "1") (pinfunction "1_1") (pintype "passive"))
      (node (ref "D12") (pin "C") (pinfunction "C_C") (pintype "bidirectional"))
      (node (ref "IC4") (pin "P30") (pinfunction "VEE_D_P30") (pintype "bidirectional"))
    )
    (net (code "82") (name "Net-(IC4-VEE_DIS)") (class "Default")
      (node (ref "IC4") (pin "P29") (pinfunction "VEE_DIS_P29") (pintype "bidirectional"))
      (node (ref "R20") (pin "1") (pinfunction "1_1") (pintype "passive"))
    )
    (net (code "83") (name "Net-(IC4-VEE_DRV)") (class "Default")
      (node (ref "C45") (pin "1") (pinfunction "1_1") (pintype "passive"))
      (node (ref "IC4") (pin "P28") (pinfunction "VEE_DRV_P28") (pintype "bidirectional"))
    )
    (net (code "84") (name "Net-(IC4-VEE_FB)") (class "Default")
      (node (ref "IC4") (pin "P31") (pinfunction "VEE_FB_P31") (pintype "bidirectional"))
      (node (ref "R11") (pin "1") (pinfunction "1_1") (pintype "passive"))
      (node (ref "R12") (pin "2") (pinfunction "2_2") (pintype "passive"))
    )
    (net (code "85") (name "Net-(IC4-VNEG_DIS)") (class "Default")
      (node (ref "IC4") (pin "P$9") (pinfunction "VNEG_DIS_P$9") (pintype "bidirectional"))
      (node (ref "R16") (pin "1") (pinfunction "1_1") (pintype "passive"))
    )
    (net (code "86") (name "Net-(IC4-VN_SW)") (class "Default")
      (node (ref "D9") (pin "C") (pinfunction "C_C") (pintype "bidirectional"))
      (node (ref "IC4") (pin "P25") (pinfunction "VN_SW_P25") (pintype "bidirectional"))
      (node (ref "L4") (pin "P$1") (pinfunction "P$1_P$1") (pintype "bidirectional"))
    )
    (net (code "87") (name "Net-(IC4-VPOS_DIS)") (class "Default")
      (node (ref "IC4") (pin "P19") (pinfunction "VPOS_DIS_P19") (pintype "bidirectional"))
      (node (ref "R18") (pin "1") (pinfunction "1_1") (pintype "passive"))
    )
    (net (code "88") (name "Net-(IC4-VREF)") (class "Default")
      (node (ref "C44") (pin "1") (pinfunction "1_1") (pintype "passive"))
      (node (ref "IC4") (pin "P$1") (pinfunction "VREF_P$1") (pintype "bidirectional"))
    )
    (net (code "89") (name "Net-(IC5-FB)") (class "Default")
      (node (ref "C17") (pin "1") (pinfunction "1_1") (pintype "passive"))
      (node (ref "IC5") (pin "5") (pinfunction "FB_5") (pintype "bidirectional"))
      (node (ref "R8") (pin "2") (pinfunction "2_2") (pintype "passive"))
      (node (ref "R9") (pin "2") (pinfunction "2_2") (pintype "passive"))
    )
    (net (code "90") (name "Net-(IC5-SW)") (class "Default")
      (node (ref "IC5") (pin "3") (pinfunction "SW_3") (pintype "bidirectional"))
      (node (ref "L1") (pin "P$1") (pinfunction "P$1_P$1") (pintype "bidirectional"))
    )
    (net (code "91") (name "Net-(IC6-FB)") (class "Default")
      (node (ref "C23") (pin "1") (pinfunction "1_1") (pintype "passive"))
      (node (ref "IC6") (pin "5") (pinfunction "FB_5") (pintype "bidirectional"))
      (node (ref "R10") (pin "2") (pinfunction "2_2") (pintype "passive"))
      (node (ref "R21") (pin "2") (pinfunction "2_2") (pintype "passive"))
    )
    (net (code "92") (name "Net-(IC6-SW)") (class "Default")
      (node (ref "IC6") (pin "3") (pinfunction "SW_3") (pintype "bidirectional"))
      (node (ref "L2") (pin "P$1") (pinfunction "P$1_P$1") (pintype "bidirectional"))
    )
    (net (code "93") (name "Net-(LED1-PadC)") (class "Default")
      (node (ref "LED1") (pin "C") (pinfunction "C_C") (pintype "passive"))
      (node (ref "R7") (pin "2") (pinfunction "2_2") (pintype "passive"))
    )
    (net (code "94") (name "Net-(LED2-PadA)") (class "Default")
      (node (ref "LED2") (pin "A") (pinfunction "A_A") (pintype "passive"))
      (node (ref "R22") (pin "2") (pinfunction "2_2") (pintype "passive"))
    )
    (net (code "95") (name "PG_PIN") (class "Default")
      (node (ref "IC4") (pin "P23") (pinfunction "PWR_GOOD_P23") (pintype "bidirectional"))
      (node (ref "LED2") (pin "C") (pinfunction "C_C") (pintype "passive"))
    )
    (net (code "96") (name "SCL_PIN") (class "Default")
      (node (ref "IC4") (pin "P17") (pinfunction "SCL_P17") (pintype "bidirectional"))
      (node (ref "J2") (pin "11") (pinfunction "11_11") (pintype "passive"))
    )
    (net (code "97") (name "SDA_PIN") (class "Default")
      (node (ref "IC4") (pin "P18") (pinfunction "SDA_P18") (pintype "bidirectional"))
      (node (ref "J2") (pin "12") (pinfunction "12_12") (pintype "passive"))
    )
    (net (code "98") (name "SPI_CLK") (class "Default")
      (node (ref "IC1") (pin "1") (pinfunction "IOL_1A_1") (pintype "bidirectional"))
      (node (ref "J2") (pin "1") (pinfunction "1_1") (pintype "passive"))
    )
    (net (code "99") (name "SPI_CMD") (class "Default")
      (node (ref "IC1") (pin "8") (pinfunction "IOL_3B_8") (pintype "bidirectional"))
      (node (ref "J2") (pin "7") (pinfunction "7_7") (pintype "passive"))
    )
    (net (code "100") (name "SPI_CS") (class "Default")
      (node (ref "IC1") (pin "9") (pinfunction "IOL_5A_9") (pintype "bidirectional"))
      (node (ref "J2") (pin "6") (pinfunction "6_6") (pintype "passive"))
    )
    (net (code "101") (name "SPI_DATA0") (class "Default")
      (node (ref "IC1") (pin "2") (pinfunction "IOL_1B_2") (pintype "bidirectional"))
      (node (ref "J2") (pin "2") (pinfunction "2_2") (pintype "passive"))
    )
    (net (code "102") (name "SPI_DATA1") (class "Default")
      (node (ref "IC1") (pin "3") (pinfunction "IOL_2A_3") (pintype "bidirectional"))
      (node (ref "J2") (pin "3") (pinfunction "3_3") (pintype "passive"))
    )
    (net (code "103") (name "SPI_DATA2") (class "Default")
      (node (ref "IC1") (pin "4") (pinfunction "IOL_2B_4") (pintype "bidirectional"))
      (node (ref "J2") (pin "4") (pinfunction "4_4") (pintype "passive"))
    )
    (net (code "104") (name "SPI_DATA3") (class "Default")
      (node (ref "IC1") (pin "7") (pinfunction "IOL_3A_7") (pintype "bidirectional"))
      (node (ref "J2") (pin "5") (pinfunction "5_5") (pintype "passive"))
    )
    (net (code "105") (name "VB") (class "Default")
      (node (ref "C35") (pin "1") (pinfunction "1_1") (pintype "passive"))
      (node (ref "C36") (pin "1") (pinfunction "1_1") (pintype "passive"))
      (node (ref "D8") (pin "C") (pinfunction "C_C") (pintype "bidirectional"))
      (node (ref "IC4") (pin "P37") (pinfunction "VDDH_IN_P37") (pintype "bidirectional"))
      (node (ref "IC4") (pin "P42") (pinfunction "VB_P42") (pintype "bidirectional"))
      (node (ref "IC4") (pin "P43") (pinfunction "VPOS_IN_P43") (pintype "bidirectional"))
    )
    (net (code "106") (name "VIN") (class "Default")
      (node (ref "C21") (pin "1") (pinfunction "1_1") (pintype "passive"))
      (node (ref "C24") (pin "1") (pinfunction "1_1") (pintype "passive"))
      (node (ref "IC5") (pin "1") (pinfunction "EN_1") (pintype "bidirectional"))
      (node (ref "IC5") (pin "4") (pinfunction "VIN_4") (pintype "bidirectional"))
      (node (ref "IC6") (pin "1") (pinfunction "EN_1") (pintype "bidirectional"))
      (node (ref "IC6") (pin "4") (pinfunction "VIN_4") (pintype "bidirectional"))
      (node (ref "J2") (pin "14") (pinfunction "14_14") (pintype "passive"))
    )
    (net (code "107") (name "VN") (class "Default")
      (node (ref "C37") (pin "1") (pinfunction "1_1") (pintype "passive"))
      (node (ref "C41") (pin "1") (pinfunction "1_1") (pintype "passive"))
      (node (ref "C42") (pin "1") (pinfunction "1_1") (pintype "passive"))
      (node (ref "D9") (pin "A") (pinfunction "A_A") (pintype "bidirectional"))
      (node (ref "IC4") (pin "GN0") (pinfunction "POWER_PAD_GN0") (pintype "bidirectional"))
      (node (ref "IC4") (pin "GN1") (pinfunction "POWER_PAD_GN1") (pintype "bidirectional"))
      (node (ref "IC4") (pin "GN10") (pinfunction "POWER_PAD_GN10") (pintype "bidirectional"))
      (node (ref "IC4") (pin "GN11") (pinfunction "POWER_PAD_GN11") (pintype "bidirectional"))
      (node (ref "IC4") (pin "GN12") (pinfunction "POWER_PAD_GN12") (pintype "bidirectional"))
      (node (ref "IC4") (pin "GN13") (pinfunction "POWER_PAD_GN13") (pintype "bidirectional"))
      (node (ref "IC4") (pin "GN14") (pinfunction "POWER_PAD_GN14") (pintype "bidirectional"))
      (node (ref "IC4") (pin "GN15") (pinfunction "POWER_PAD_GN15") (pintype "bidirectional"))
      (node (ref "IC4") (pin "GN16") (pinfunction "POWER_PAD_GN16") (pintype "bidirectional"))
      (node (ref "IC4") (pin "GN2") (pinfunction "POWER_PAD_GN2") (pintype "bidirectional"))
      (node (ref "IC4") (pin "GN3") (pinfunction "POWER_PAD_GN3") (pintype "bidirectional"))
      (node (ref "IC4") (pin "GN4") (pinfunction "POWER_PAD_GN4") (pintype "bidirectional"))
      (node (ref "IC4") (pin "GN5") (pinfunction "POWER_PAD_GN5") (pintype "bidirectional"))
      (node (ref "IC4") (pin "GN6") (pinfunction "POWER_PAD_GN6") (pintype "bidirectional"))
      (node (ref "IC4") (pin "GN7") (pinfunction "POWER_PAD_GN7") (pintype "bidirectional"))
      (node (ref "IC4") (pin "GN8") (pinfunction "POWER_PAD_GN8") (pintype "bidirectional"))
      (node (ref "IC4") (pin "GN9") (pinfunction "POWER_PAD_GN9") (pintype "bidirectional"))
      (node (ref "IC4") (pin "P$4") (pinfunction "VNEG_IN_P$4") (pintype "bidirectional"))
      (node (ref "IC4") (pin "P16") (pinfunction "VCOM_PWR_P16") (pintype "bidirectional"))
      (node (ref "IC4") (pin "P22") (pinfunction "PBKG_P22") (pintype "bidirectional"))
      (node (ref "IC4") (pin "P26") (pinfunction "VN_P26") (pintype "bidirectional"))
      (node (ref "IC4") (pin "P27") (pinfunction "VEE_IN_P27") (pintype "bidirectional"))
    )
    (net (code "108") (name "WAKE_PIN") (class "Default")
      (node (ref "IC4") (pin "P$5") (pinfunction "WAKEUP_P$5") (pintype "bidirectional"))
      (node (ref "J2") (pin "9") (pinfunction "9_9") (pintype "passive"))
    )
    (net (code "109") (name "unconnected-(IC1-IOL_5B-Pad10)") (class "Default")
      (node (ref "IC1") (pin "10") (pinfunction "IOL_5B_10") (pintype "bidirectional"))
    )
    (net (code "110") (name "unconnected-(IC1-IOL_6A-Pad12)") (class "Default")
      (node (ref "IC1") (pin "12") (pinfunction "IOL_6A_12") (pintype "bidirectional"))
    )
    (net (code "111") (name "unconnected-(IC1-IOL_6B_GBIN7-Pad13)") (class "Default")
      (node (ref "IC1") (pin "13") (pinfunction "IOL_6B_GBIN7_13") (pintype "bidirectional"))
    )
    (net (code "112") (name "unconnected-(IC1-IOL_7B-Pad16)") (class "Default")
      (node (ref "IC1") (pin "16") (pinfunction "IOL_7B_16") (pintype "bidirectional"))
    )
    (net (code "113") (name "unconnected-(IC1-IOL_8A-Pad18)") (class "Default")
      (node (ref "IC1") (pin "18") (pinfunction "IOL_8A_18") (pintype "bidirectional"))
    )
    (net (code "114") (name "unconnected-(IC1-IOL_8B-Pad19)") (class "Default")
      (node (ref "IC1") (pin "19") (pinfunction "IOL_8B_19") (pintype "bidirectional"))
    )
    (net (code "115") (name "unconnected-(IC1-IOL_10A-Pad20)") (class "Default")
      (node (ref "IC1") (pin "20") (pinfunction "IOL_10A_20") (pintype "bidirectional"))
    )
    (net (code "116") (name "unconnected-(IC1-VPP_FAST-Pad76)") (class "Default")
      (node (ref "IC1") (pin "76") (pinfunction "VPP_FAST_76") (pintype "bidirectional"))
    )
    (net (code "117") (name "unconnected-(IC4-V3P3-PadP46)") (class "Default")
      (node (ref "IC4") (pin "P46") (pinfunction "V3P3_P46") (pintype "bidirectional"))
    )
    (net (code "118") (name "unconnected-(J1-P$4-Pad4)") (class "Default")
      (node (ref "J1") (pin "4") (pinfunction "P$4_4") (pintype "bidirectional"))
    )
    (net (code "119") (name "unconnected-(J1-P$5-Pad5)") (class "Default")
      (node (ref "J1") (pin "5") (pinfunction "P$5_5") (pintype "bidirectional"))
    )
    (net (code "120") (name "unconnected-(J1-P$22-Pad22)") (class "Default")
      (node (ref "J1") (pin "22") (pinfunction "P$22_22") (pintype "bidirectional"))
    )
    (net (code "121") (name "unconnected-(J1-P$23-Pad23)") (class "Default")
      (node (ref "J1") (pin "23") (pinfunction "P$23_23") (pintype "bidirectional"))
    )
    (net (code "122") (name "unconnected-(J1-P$24-Pad24)") (class "Default")
      (node (ref "J1") (pin "24") (pinfunction "P$24_24") (pintype "bidirectional"))
    )
    (net (code "123") (name "unconnected-(J1-P$25-Pad25)") (class "Default")
      (node (ref "J1") (pin "25") (pinfunction "P$25_25") (pintype "bidirectional"))
    )
    (net (code "124") (name "unconnected-(J1-P$30-Pad30)") (class "Default")
      (node (ref "J1") (pin "30") (pinfunction "P$30_30") (pintype "bidirectional"))
    )
    (net (code "125") (name "unconnected-(X1-Pad1)") (class "Default")
      (node (ref "X1") (pin "1") (pinfunction "1_1") (pintype "bidirectional"))
    )
    (net (code "126") (name "~{CE}") (class "Default")
      (node (ref "IC1") (pin "54") (pinfunction "IOR_55_54") (pintype "bidirectional"))
      (node (ref "IC2") (pin "6") (pinfunction "~{CE}_6") (pintype "bidirectional"))
      (node (ref "R4") (pin "2") (pinfunction "2_2") (pintype "passive"))
    )
    (net (code "127") (name "~{OE}") (class "Default")
      (node (ref "IC1") (pin "51") (pinfunction "IOR_52_51") (pintype "bidirectional"))
      (node (ref "IC2") (pin "41") (pinfunction "~{OE}_41") (pintype "bidirectional"))
    )
    (net (code "128") (name "~{WE}") (class "Default")
      (node (ref "IC1") (pin "74") (pinfunction "IOR_72_74") (pintype "bidirectional"))
      (node (ref "IC2") (pin "17") (pinfunction "~{WE}_17") (pintype "bidirectional"))
    )
  )
)
